# BMP085_HIH6130.net
KiCad netlist of a schematic drawn in EAGLE
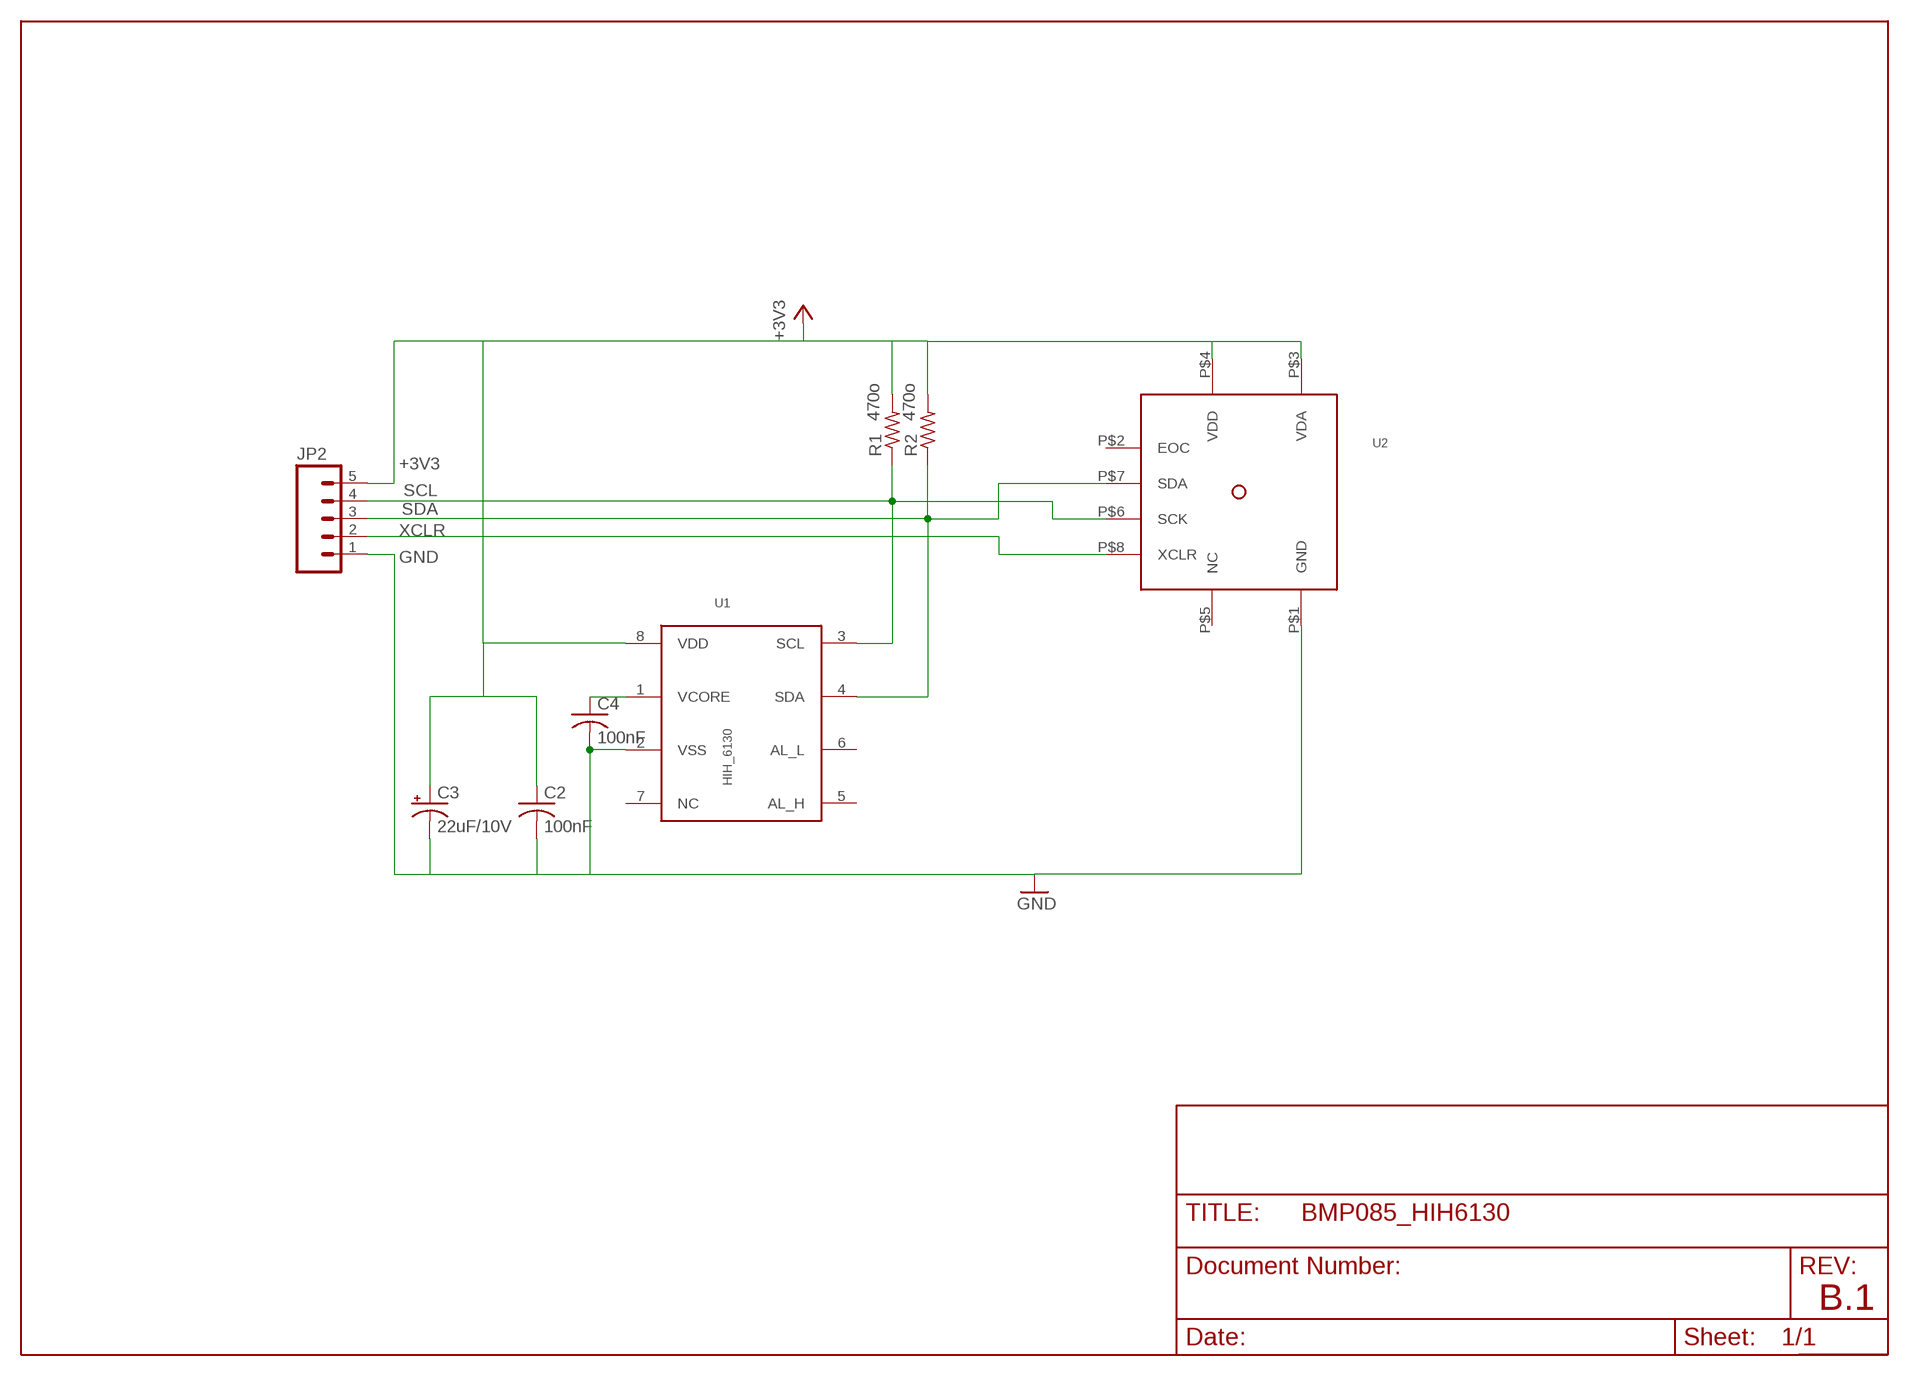
[diagram p0: schematic, sheet 1]

(export (version "E")
  (design (tool "Eeschema 10.0.6"))
  (components
    (comp (ref "C2")
      (value "100nF")
      (footprint "eagle-import:C0805K")
      (libsource (lib "eagle-import") (part "C-USC0805K"))
    )
    (comp (ref "C3")
      (value "22uF/10V")
      (footprint "eagle-import:SMC_B")
      (libsource (lib "eagle-import") (part "CPOL-USSMCB"))
    )
    (comp (ref "C4")
      (value "100nF")
      (footprint "eagle-import:C0805K")
      (libsource (lib "eagle-import") (part "C-USC0805K"))
    )
    (comp (ref "JP2")
      (value "M05PTH")
      (footprint "eagle-import:1X05")
      (libsource (lib "eagle-import") (part "M05PTH"))
    )
    (comp (ref "R1")
      (value "470o")
      (footprint "eagle-import:R0603")
      (libsource (lib "eagle-import") (part "R-US_R0603"))
    )
    (comp (ref "R2")
      (value "470o")
      (footprint "eagle-import:R0603")
      (libsource (lib "eagle-import") (part "R-US_R0603"))
    )
    (comp (ref "U1")
      (value "HIH_6130")
      (footprint "eagle-import:SOIC8")
      (libsource (lib "eagle-import") (part "HIH_6130"))
    )
    (comp (ref "U2")
      (value "BMP085")
      (footprint "eagle-import:LCC8")
      (libsource (lib "eagle-import") (part "BMP085"))
    )
  )
  (nets
    (net (code "1") (name "+3V3") (class "Default")
      (node (ref "C2") (pin "1") (pinfunction "1_1") (pintype "passive"))
      (node (ref "C3") (pin "+") (pinfunction "+_+") (pintype "passive"))
      (node (ref "JP2") (pin "5") (pinfunction "5_5") (pintype "passive"))
      (node (ref "R1") (pin "2") (pinfunction "2_2") (pintype "passive"))
      (node (ref "R2") (pin "2") (pinfunction "2_2") (pintype "passive"))
      (node (ref "U1") (pin "8") (pinfunction "VDD_8") (pintype "bidirectional"))
      (node (ref "U2") (pin "P$3") (pinfunction "VDA_P$3") (pintype "power_in"))
      (node (ref "U2") (pin "P$4") (pinfunction "VDD_P$4") (pintype "power_in"))
    )
    (net (code "2") (name "/SCL") (class "Default")
      (node (ref "JP2") (pin "4") (pinfunction "4_4") (pintype "passive"))
      (node (ref "R1") (pin "1") (pinfunction "1_1") (pintype "passive"))
      (node (ref "U1") (pin "3") (pinfunction "SCL_3") (pintype "bidirectional"))
      (node (ref "U2") (pin "P$6") (pinfunction "SCK_P$6") (pintype "input"))
    )
    (net (code "3") (name "/SDA") (class "Default")
      (node (ref "JP2") (pin "3") (pinfunction "3_3") (pintype "passive"))
      (node (ref "R2") (pin "1") (pinfunction "1_1") (pintype "passive"))
      (node (ref "U1") (pin "4") (pinfunction "SDA_4") (pintype "bidirectional"))
      (node (ref "U2") (pin "P$7") (pinfunction "SDA_P$7") (pintype "bidirectional"))
    )
    (net (code "4") (name "/XCLR") (class "Default")
      (node (ref "JP2") (pin "2") (pinfunction "2_2") (pintype "passive"))
      (node (ref "U2") (pin "P$8") (pinfunction "XCLR_P$8") (pintype "input"))
    )
    (net (code "5") (name "GND") (class "Default")
      (node (ref "C2") (pin "2") (pinfunction "2_2") (pintype "passive"))
      (node (ref "C3") (pin "-") (pinfunction "-_-") (pintype "passive"))
      (node (ref "C4") (pin "2") (pinfunction "2_2") (pintype "passive"))
      (node (ref "JP2") (pin "1") (pinfunction "1_1") (pintype "passive"))
      (node (ref "U1") (pin "2") (pinfunction "VSS_2") (pintype "bidirectional"))
      (node (ref "U2") (pin "P$1") (pinfunction "GND_P$1") (pintype "power_in"))
    )
    (net (code "6") (name "Net-(U1-VCORE)") (class "Default")
      (node (ref "C4") (pin "1") (pinfunction "1_1") (pintype "passive"))
      (node (ref "U1") (pin "1") (pinfunction "VCORE_1") (pintype "bidirectional"))
    )
    (net (code "7") (name "unconnected-(U1-AL_H-Pad5)") (class "Default")
      (node (ref "U1") (pin "5") (pinfunction "AL_H_5") (pintype "bidirectional"))
    )
    (net (code "8") (name "unconnected-(U1-AL_L-Pad6)") (class "Default")
      (node (ref "U1") (pin "6") (pinfunction "AL_L_6") (pintype "bidirectional"))
    )
    (net (code "9") (name "unconnected-(U1-NC-Pad7)") (class "Default")
      (node (ref "U1") (pin "7") (pinfunction "NC_7") (pintype "bidirectional"))
    )
    (net (code "10") (name "unconnected-(U2-EOC-PadP$2)") (class "Default")
      (node (ref "U2") (pin "P$2") (pinfunction "EOC_P$2") (pintype "output"))
    )
    (net (code "11") (name "unconnected-(U2-NC-PadP$5)") (class "Default")
      (node (ref "U2") (pin "P$5") (pinfunction "NC_P$5") (pintype "no_connect"))
    )
  )
)
